# 2-MCP23S17.net
KiCad netlist of a schematic drawn in Altium Designer
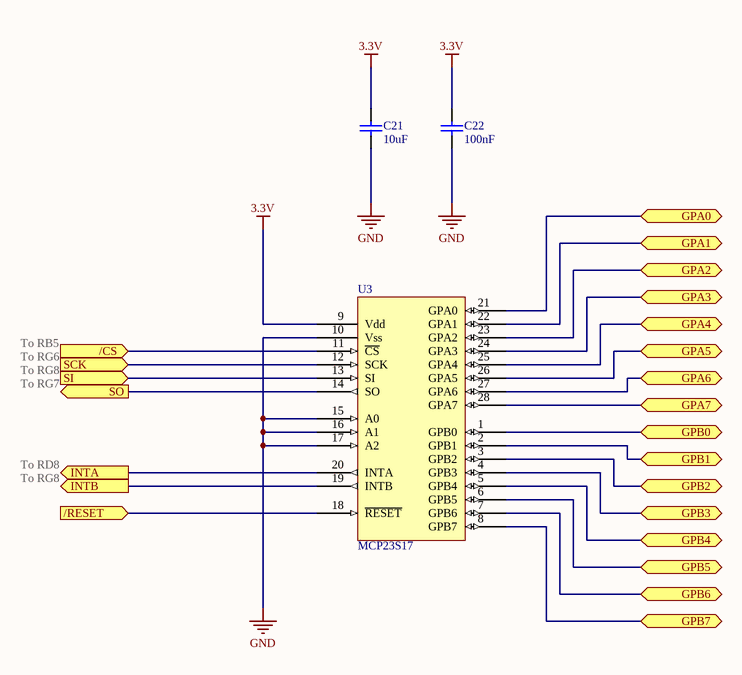
[diagram p0: 2-MCP23S17.SchDoc]

(export (version "E")
  (design (tool "Eeschema 10.0.6"))
  (components
    (comp (ref "C21")
      (value "10uF")
      (footprint "capa 1206")
      (description "Capacitor")
      (libsource (lib "Miscellaneous Devices") (part "Cap"))
    )
    (comp (ref "C22")
      (value "100nF")
      (footprint "capa 1206")
      (description "Capacitor")
      (libsource (lib "Miscellaneous Devices") (part "Cap"))
    )
    (comp (ref "U3")
      (value "MCP23S17")
      (footprint "MCP23S17-E/SO")
      (libsource (lib "0x2a002a") (part "MCP23S17"))
    )
  )
  (nets
    (net (code "1") (name "/GPA0") (class "Default")
      (node (ref "U3") (pin "21") (pinfunction "GPA0_21") (pintype "bidirectional"))
    )
    (net (code "2") (name "/GPA1") (class "Default")
      (node (ref "U3") (pin "22") (pinfunction "GPA1_22") (pintype "bidirectional"))
    )
    (net (code "3") (name "/GPA2") (class "Default")
      (node (ref "U3") (pin "23") (pinfunction "GPA2_23") (pintype "bidirectional"))
    )
    (net (code "4") (name "/GPA3") (class "Default")
      (node (ref "U3") (pin "24") (pinfunction "GPA3_24") (pintype "bidirectional"))
    )
    (net (code "5") (name "/GPA4") (class "Default")
      (node (ref "U3") (pin "25") (pinfunction "GPA4_25") (pintype "bidirectional"))
    )
    (net (code "6") (name "/GPA5") (class "Default")
      (node (ref "U3") (pin "26") (pinfunction "GPA5_26") (pintype "bidirectional"))
    )
    (net (code "7") (name "/GPA6") (class "Default")
      (node (ref "U3") (pin "27") (pinfunction "GPA6_27") (pintype "bidirectional"))
    )
    (net (code "8") (name "/GPA7") (class "Default")
      (node (ref "U3") (pin "28") (pinfunction "GPA7_28") (pintype "bidirectional"))
    )
    (net (code "9") (name "/GPB0") (class "Default")
      (node (ref "U3") (pin "1") (pinfunction "GPB0_1") (pintype "bidirectional"))
    )
    (net (code "10") (name "/GPB1") (class "Default")
      (node (ref "U3") (pin "2") (pinfunction "GPB1_2") (pintype "bidirectional"))
    )
    (net (code "11") (name "/GPB2") (class "Default")
      (node (ref "U3") (pin "3") (pinfunction "GPB2_3") (pintype "bidirectional"))
    )
    (net (code "12") (name "/GPB3") (class "Default")
      (node (ref "U3") (pin "4") (pinfunction "GPB3_4") (pintype "bidirectional"))
    )
    (net (code "13") (name "/GPB4") (class "Default")
      (node (ref "U3") (pin "5") (pinfunction "GPB4_5") (pintype "bidirectional"))
    )
    (net (code "14") (name "/GPB5") (class "Default")
      (node (ref "U3") (pin "6") (pinfunction "GPB5_6") (pintype "bidirectional"))
    )
    (net (code "15") (name "/GPB6") (class "Default")
      (node (ref "U3") (pin "7") (pinfunction "GPB6_7") (pintype "bidirectional"))
    )
    (net (code "16") (name "/GPB7") (class "Default")
      (node (ref "U3") (pin "8") (pinfunction "GPB7_8") (pintype "bidirectional"))
    )
    (net (code "17") (name "/INTA") (class "Default")
      (node (ref "U3") (pin "20") (pinfunction "INTA_20") (pintype "output"))
    )
    (net (code "18") (name "/INTB") (class "Default")
      (node (ref "U3") (pin "19") (pinfunction "INTB_19") (pintype "output"))
    )
    (net (code "19") (name "/SCK") (class "Default")
      (node (ref "U3") (pin "12") (pinfunction "SCK_12") (pintype "input"))
    )
    (net (code "20") (name "/SI") (class "Default")
      (node (ref "U3") (pin "13") (pinfunction "SI_13") (pintype "input"))
    )
    (net (code "21") (name "/SO") (class "Default")
      (node (ref "U3") (pin "14") (pinfunction "SO_14") (pintype "output"))
    )
    (net (code "22") (name "/{slash}CS") (class "Default")
      (node (ref "U3") (pin "11") (pinfunction "~{CS}_11") (pintype "input"))
    )
    (net (code "23") (name "/{slash}RESET") (class "Default")
      (node (ref "U3") (pin "18") (pinfunction "~{RESET}_18") (pintype "input"))
    )
    (net (code "24") (name "3.3V") (class "Default")
      (node (ref "C21") (pin "1") (pinfunction "1_1") (pintype "passive"))
      (node (ref "C22") (pin "1") (pinfunction "1_1") (pintype "passive"))
      (node (ref "U3") (pin "9") (pinfunction "Vdd_9") (pintype "power_in"))
    )
    (net (code "25") (name "GND") (class "Default")
      (node (ref "C21") (pin "2") (pinfunction "2_2") (pintype "passive"))
      (node (ref "C22") (pin "2") (pinfunction "2_2") (pintype "passive"))
      (node (ref "U3") (pin "10") (pinfunction "Vss_10") (pintype "power_in"))
      (node (ref "U3") (pin "15") (pinfunction "A0_15") (pintype "input"))
      (node (ref "U3") (pin "16") (pinfunction "A1_16") (pintype "input"))
      (node (ref "U3") (pin "17") (pinfunction "A2_17") (pintype "input"))
    )
  )
)
